# USB.net
KiCad netlist of a schematic drawn in Altium Designer
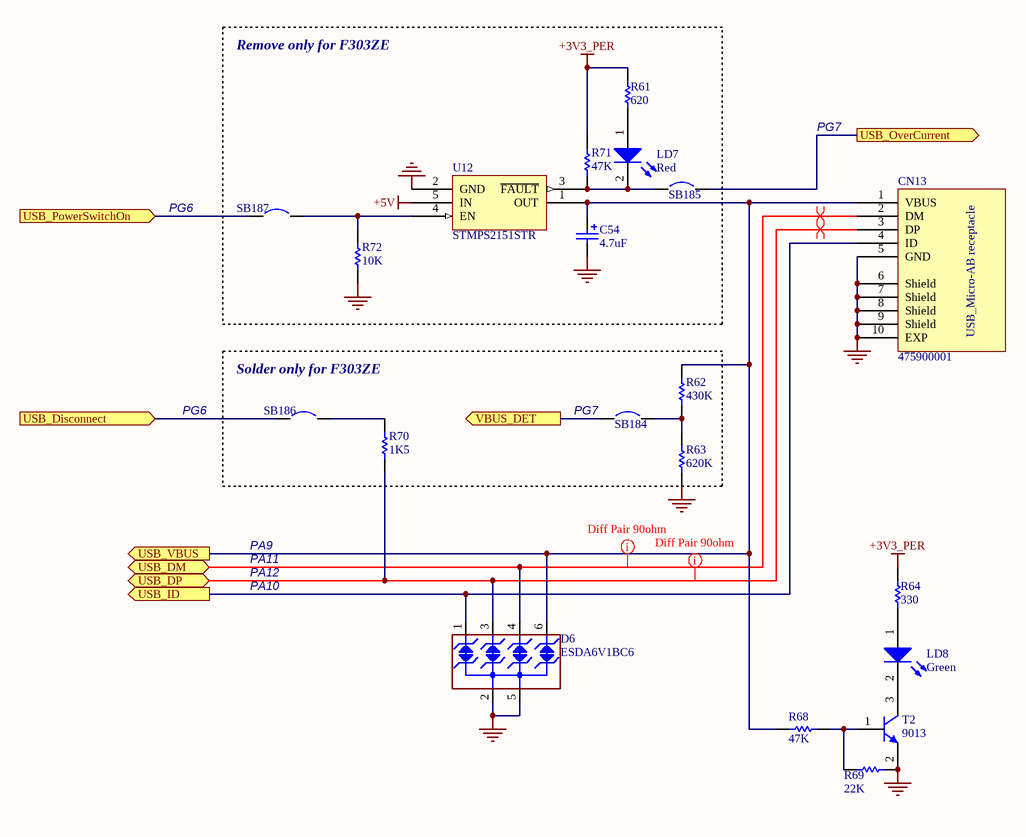
[diagram p0: USB.SchDoc]

(export (version "E")
  (design (tool "Eeschema 10.0.6"))
  (components
    (comp (ref "C54")
      (value "4.7uF")
      (footprint "TAN-A")
      (description "Polarized Capacitor (Radial)")
      (fields (field (name "PUBLISHER") "Altium Limited"))
      (libsource (lib "Miscellaneous Devices") (part "Cap Pol1"))
    )
    (comp (ref "CN13")
      (value "475900001")
      (footprint "MOLEX_47590001")
      (libsource (lib "mb1045") (part "475900001"))
    )
    (comp (ref "D6")
      (value "ESDA6V1BC6")
      (footprint "STM-SMEE:SOT23-6L")
      (description "Dual Transil array for ESD protection")
      (libsource (lib "MB1137") (part "ESDA6V1BC6"))
    )
    (comp (ref "LD7")
      (value "Red")
      (footprint "0603D-R")
      (description "Typical RED, GREEN, YELLOW, AMBER GaAs LED")
      (fields (field (name "PUBLISHER") "Altium Limited"))
      (libsource (lib "Miscellaneous Devices") (part "LED2"))
    )
    (comp (ref "LD8")
      (value "Green")
      (footprint "0603D-G")
      (description "Typical RED, GREEN, YELLOW, AMBER GaAs LED")
      (fields (field (name "PUBLISHER") "Altium Limited"))
      (libsource (lib "Miscellaneous Devices") (part "LED2"))
    )
    (comp (ref "R61")
      (value "620")
      (footprint "0603R")
      (description "Resistor")
      (fields (field (name "PUBLISHER") "Altium Limited"))
      (libsource (lib "Miscellaneous Devices") (part "Res1"))
    )
    (comp (ref "R62")
      (value "430K")
      (footprint "0603R")
      (description "Resistor")
      (fields (field (name "PUBLISHER") "Altium Limited"))
      (libsource (lib "Miscellaneous Devices") (part "res1"))
    )
    (comp (ref "R63")
      (value "620K")
      (footprint "0603R")
      (description "Resistor")
      (fields (field (name "PUBLISHER") "Altium Limited"))
      (libsource (lib "Miscellaneous Devices") (part "res1"))
    )
    (comp (ref "R64")
      (value "330")
      (footprint "0603R")
      (description "Resistor")
      (fields (field (name "PUBLISHER") "Altium Limited"))
      (libsource (lib "Miscellaneous Devices") (part "res1"))
    )
    (comp (ref "R68")
      (value "47K")
      (footprint "0603R")
      (description "Resistor")
      (fields (field (name "PUBLISHER") "Altium Limited"))
      (libsource (lib "Miscellaneous Devices") (part "res1"))
    )
    (comp (ref "R69")
      (value "22K")
      (footprint "0603R")
      (description "Resistor")
      (fields (field (name "PUBLISHER") "Altium Limited"))
      (libsource (lib "Miscellaneous Devices") (part "res1"))
    )
    (comp (ref "R70")
      (value "1K5")
      (footprint "0603R")
      (description "Resistor 0402 or 0603 or 0805")
      (libsource (lib "") (part "Res1_1"))
    )
    (comp (ref "R71")
      (value "47K")
      (footprint "0603R")
      (description "Resistor")
      (fields (field (name "PUBLISHER") "Altium Limited"))
      (libsource (lib "Miscellaneous Devices") (part "res1"))
    )
    (comp (ref "R72")
      (value "10K")
      (footprint "0603R")
      (description "Resistor")
      (fields (field (name "PUBLISHER") "Altium Limited"))
      (libsource (lib "Miscellaneous Devices") (part "Res1"))
    )
    (comp (ref "SB184")
      (value "Circuit Breaker")
      (footprint "SB_0603")
      (fields (field (name "PUBLISHER") "Altium Limited"))
      (libsource (lib "MCD_TOOLS") (part "Circuit Breaker"))
    )
    (comp (ref "SB185")
      (value "Circuit Breaker")
      (footprint "SB_0603")
      (fields (field (name "PUBLISHER") "Altium Limited"))
      (libsource (lib "MCD_TOOLS") (part "Circuit Breaker"))
    )
    (comp (ref "SB186")
      (value "Circuit Breaker")
      (footprint "SB_0603")
      (fields (field (name "PUBLISHER") "Altium Limited"))
      (libsource (lib "MCD_TOOLS") (part "Circuit Breaker"))
    )
    (comp (ref "SB187")
      (value "Circuit Breaker")
      (footprint "SB_0603")
      (fields (field (name "PUBLISHER") "Altium Limited"))
      (libsource (lib "MCD_TOOLS") (part "Circuit Breaker"))
    )
    (comp (ref "T2")
      (value "9013")
      (footprint "SOT-23")
      (description "NPN Bipolar Transistor")
      (fields (field (name "PUBLISHER") "Altium Limited"))
      (libsource (lib "MB1167") (part "NPN"))
    )
    (comp (ref "U12")
      (value "STMPS2151STR")
      (footprint "SOT-23-5L")
      (libsource (lib "mb1045") (part "STMPS2141STR"))
    )
  )
  (nets
    (net (code "1") (name "+3V3_PER") (class "Default")
      (node (ref "R61") (pin "2") (pinfunction "2_2") (pintype "passive"))
      (node (ref "R64") (pin "2") (pinfunction "2_2") (pintype "passive"))
      (node (ref "R71") (pin "1") (pinfunction "1_1") (pintype "passive"))
    )
    (net (code "2") (name "+5V") (class "Default")
      (node (ref "U12") (pin "5") (pinfunction "IN_5") (pintype "passive"))
    )
    (net (code "3") (name "/USB_DM") (class "Default")
      (node (ref "CN13") (pin "2") (pinfunction "DM_2") (pintype "passive"))
      (node (ref "D6") (pin "4") (pinfunction "IO3_4") (pintype "passive"))
    )
    (net (code "4") (name "/USB_DP") (class "Default")
      (node (ref "CN13") (pin "3") (pinfunction "DP_3") (pintype "passive"))
      (node (ref "D6") (pin "3") (pinfunction "GND_3") (pintype "passive"))
      (node (ref "R70") (pin "1") (pinfunction "1_1") (pintype "passive"))
    )
    (net (code "5") (name "/USB_Disconnect") (class "Default")
      (node (ref "SB186") (pin "1") (pinfunction "1_1") (pintype "passive"))
    )
    (net (code "6") (name "/USB_ID") (class "Default")
      (node (ref "CN13") (pin "4") (pinfunction "ID_4") (pintype "passive"))
      (node (ref "D6") (pin "1") (pinfunction "IO1_1") (pintype "passive"))
    )
    (net (code "7") (name "/USB_OverCurrent") (class "Default")
      (node (ref "SB185") (pin "2") (pinfunction "2_2") (pintype "passive"))
    )
    (net (code "8") (name "/USB_PowerSwitchOn") (class "Default")
      (node (ref "SB187") (pin "1") (pinfunction "1_1") (pintype "passive"))
    )
    (net (code "9") (name "/USB_VBUS") (class "Default")
      (node (ref "C54") (pin "1") (pinfunction "1_1") (pintype "passive"))
      (node (ref "CN13") (pin "1") (pinfunction "VBUS_1") (pintype "passive"))
      (node (ref "D6") (pin "6") (pinfunction "NC_6") (pintype "passive"))
      (node (ref "R62") (pin "1") (pinfunction "1_1") (pintype "passive"))
      (node (ref "R68") (pin "1") (pinfunction "1_1") (pintype "passive"))
      (node (ref "U12") (pin "1") (pinfunction "OUT_1") (pintype "passive"))
    )
    (net (code "10") (name "/VBUS_DET") (class "Default")
      (node (ref "SB184") (pin "1") (pinfunction "1_1") (pintype "passive"))
    )
    (net (code "11") (name "GND") (class "Default")
      (node (ref "C54") (pin "2") (pinfunction "2_2") (pintype "passive"))
      (node (ref "CN13") (pin "10") (pinfunction "EXP_10") (pintype "passive"))
      (node (ref "CN13") (pin "5") (pinfunction "GND_5") (pintype "passive"))
      (node (ref "CN13") (pin "6") (pinfunction "Shield_6") (pintype "passive"))
      (node (ref "CN13") (pin "7") (pinfunction "Shield_7") (pintype "passive"))
      (node (ref "CN13") (pin "8") (pinfunction "Shield_8") (pintype "passive"))
      (node (ref "CN13") (pin "9") (pinfunction "Shield_9") (pintype "passive"))
      (node (ref "D6") (pin "2") (pinfunction "IO2_2") (pintype "passive"))
      (node (ref "D6") (pin "5") (pinfunction "IO4_5") (pintype "passive"))
      (node (ref "R63") (pin "2") (pinfunction "2_2") (pintype "passive"))
      (node (ref "R69") (pin "1") (pinfunction "1_1") (pintype "passive"))
      (node (ref "R72") (pin "1") (pinfunction "1_1") (pintype "passive"))
      (node (ref "T2") (pin "2") (pinfunction "E_2") (pintype "passive"))
      (node (ref "U12") (pin "2") (pinfunction "GND_2") (pintype "passive"))
    )
    (net (code "12") (name "Net-(LD7-A)") (class "Default")
      (node (ref "LD7") (pin "1") (pinfunction "A_1") (pintype "passive"))
      (node (ref "R61") (pin "1") (pinfunction "1_1") (pintype "passive"))
    )
    (net (code "13") (name "Net-(LD7-K)") (class "Default")
      (node (ref "LD7") (pin "2") (pinfunction "K_2") (pintype "passive"))
      (node (ref "R71") (pin "2") (pinfunction "2_2") (pintype "passive"))
      (node (ref "SB185") (pin "1") (pinfunction "1_1") (pintype "passive"))
      (node (ref "U12") (pin "3") (pinfunction "~{FAULT}_3") (pintype "output"))
    )
    (net (code "14") (name "Net-(LD8-A)") (class "Default")
      (node (ref "LD8") (pin "1") (pinfunction "A_1") (pintype "passive"))
      (node (ref "R64") (pin "1") (pinfunction "1_1") (pintype "passive"))
    )
    (net (code "15") (name "Net-(LD8-K)") (class "Default")
      (node (ref "LD8") (pin "2") (pinfunction "K_2") (pintype "passive"))
      (node (ref "T2") (pin "3") (pinfunction "C_3") (pintype "passive"))
    )
    (net (code "16") (name "Net-(R62-Pad2)") (class "Default")
      (node (ref "R62") (pin "2") (pinfunction "2_2") (pintype "passive"))
      (node (ref "R63") (pin "1") (pinfunction "1_1") (pintype "passive"))
      (node (ref "SB184") (pin "2") (pinfunction "2_2") (pintype "passive"))
    )
    (net (code "17") (name "Net-(R70-Pad2)") (class "Default")
      (node (ref "R70") (pin "2") (pinfunction "2_2") (pintype "passive"))
      (node (ref "SB186") (pin "2") (pinfunction "2_2") (pintype "passive"))
    )
    (net (code "18") (name "Net-(T2-B)") (class "Default")
      (node (ref "R68") (pin "2") (pinfunction "2_2") (pintype "passive"))
      (node (ref "R69") (pin "2") (pinfunction "2_2") (pintype "passive"))
      (node (ref "T2") (pin "1") (pinfunction "B_1") (pintype "passive"))
    )
    (net (code "19") (name "Net-(U12-EN)") (class "Default")
      (node (ref "R72") (pin "2") (pinfunction "2_2") (pintype "passive"))
      (node (ref "SB187") (pin "2") (pinfunction "2_2") (pintype "passive"))
      (node (ref "U12") (pin "4") (pinfunction "EN_4") (pintype "input"))
    )
  )
)
